# Main_board.net
KiCad netlist of a schematic drawn in Altium Designer
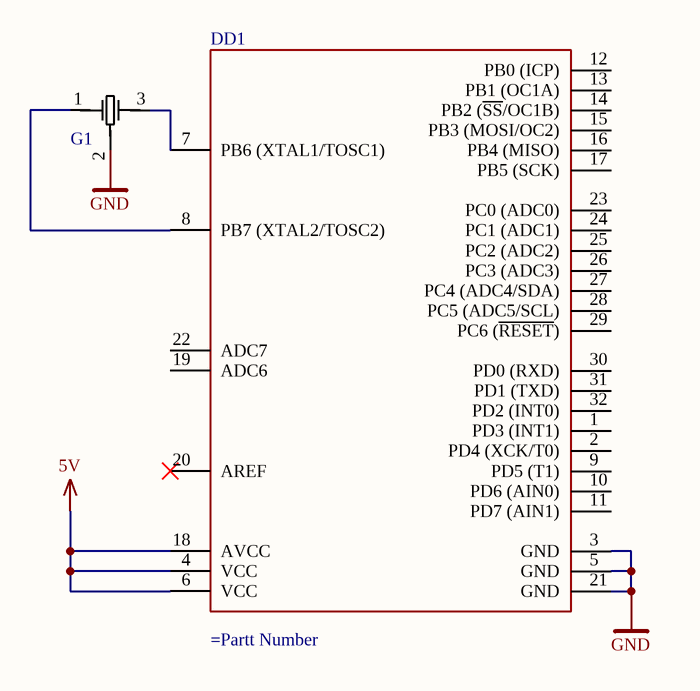
[diagram p0: Main board.SchDoc]

(export (version "E")
  (design (tool "Eeschema 10.0.6"))
  (components
    (comp (ref "DD1")
      (value "~")
      (footprint "TQFP32_N")
      (description "IC MCU 8BIT 32KB FLASH 32TQFP")
      (fields
        (field (name "PART NUMBER") "ATMEGA328")
        (field (name "DIGI-KEY PART NUMBER") "ATMEGA328PB-AU-ND")
      )
      (libsource (lib "SssAccesDatbase") (part "ATMEGA328"))
    )
    (comp (ref "G1")
      (value "8MHz 33pF")
      (footprint "CSTNE_G")
      (description "Resonators 8.0000MHz 33pF SMD CHP Resntr")
      (fields
        (field (name "PART NUMBER") "CSTNE8M00G550000R0")
        (field (name "DIGI-KEY PART NUMBER") "490-17958-1-ND")
      )
      (libsource (lib "SssAccesDatbase") (part "CSTNE_G"))
    )
  )
  (nets
    (net (code "1") (name "5V") (class "Default")
      (node (ref "DD1") (pin "18") (pinfunction "AVCC_18") (pintype "power_in"))
      (node (ref "DD1") (pin "4") (pinfunction "VCC_4") (pintype "power_in"))
      (node (ref "DD1") (pin "6") (pinfunction "VCC_6") (pintype "power_in"))
    )
    (net (code "2") (name "GND") (class "Default")
      (node (ref "DD1") (pin "21") (pinfunction "GND_21") (pintype "power_in"))
      (node (ref "DD1") (pin "3") (pinfunction "GND_3") (pintype "power_in"))
      (node (ref "DD1") (pin "5") (pinfunction "GND_5") (pintype "power_in"))
      (node (ref "G1") (pin "2") (pinfunction "2_2") (pintype "passive"))
    )
    (net (code "3") (name "Net-(DD1-PB6_(XTAL1{slash}TOSC1))") (class "Default")
      (node (ref "DD1") (pin "7") (pinfunction "PB6_(XTAL1/TOSC1)_7") (pintype "passive"))
      (node (ref "G1") (pin "3") (pinfunction "3_3") (pintype "passive"))
    )
    (net (code "4") (name "Net-(DD1-PB7_(XTAL2{slash}TOSC2))") (class "Default")
      (node (ref "DD1") (pin "8") (pinfunction "PB7_(XTAL2/TOSC2)_8") (pintype "passive"))
      (node (ref "G1") (pin "1") (pinfunction "1_1") (pintype "passive"))
    )
    (net (code "5") (name "unconnected-(DD1-ADC6-Pad19)") (class "Default")
      (node (ref "DD1") (pin "19") (pinfunction "ADC6_19") (pintype "passive"))
    )
    (net (code "6") (name "unconnected-(DD1-ADC7-Pad22)") (class "Default")
      (node (ref "DD1") (pin "22") (pinfunction "ADC7_22") (pintype "passive"))
    )
    (net (code "7") (name "unconnected-(DD1-AREF-Pad20)") (class "Default")
      (node (ref "DD1") (pin "20") (pinfunction "AREF_20") (pintype "passive+no_connect"))
    )
    (net (code "8") (name "unconnected-(DD1-PB0_(ICP)-Pad12)") (class "Default")
      (node (ref "DD1") (pin "12") (pinfunction "PB0_(ICP)_12") (pintype "passive"))
    )
    (net (code "9") (name "unconnected-(DD1-PB1_(OC1A)-Pad13)") (class "Default")
      (node (ref "DD1") (pin "13") (pinfunction "PB1_(OC1A)_13") (pintype "passive"))
    )
    (net (code "10") (name "unconnected-(DD1-PB2_(~{SS}{slash}OC1B)-Pad14)") (class "Default")
      (node (ref "DD1") (pin "14") (pinfunction "PB2_(~{SS}/OC1B)_14") (pintype "passive"))
    )
    (net (code "11") (name "unconnected-(DD1-PB3_(MOSI{slash}OC2)-Pad15)") (class "Default")
      (node (ref "DD1") (pin "15") (pinfunction "PB3_(MOSI/OC2)_15") (pintype "passive"))
    )
    (net (code "12") (name "unconnected-(DD1-PB4_(MISO)-Pad16)") (class "Default")
      (node (ref "DD1") (pin "16") (pinfunction "PB4_(MISO)_16") (pintype "passive"))
    )
    (net (code "13") (name "unconnected-(DD1-PB5_(SCK)-Pad17)") (class "Default")
      (node (ref "DD1") (pin "17") (pinfunction "PB5_(SCK)_17") (pintype "passive"))
    )
    (net (code "14") (name "unconnected-(DD1-PC0_(ADC0)-Pad23)") (class "Default")
      (node (ref "DD1") (pin "23") (pinfunction "PC0_(ADC0)_23") (pintype "passive"))
    )
    (net (code "15") (name "unconnected-(DD1-PC1_(ADC1)-Pad24)") (class "Default")
      (node (ref "DD1") (pin "24") (pinfunction "PC1_(ADC1)_24") (pintype "passive"))
    )
    (net (code "16") (name "unconnected-(DD1-PC2_(ADC2)-Pad25)") (class "Default")
      (node (ref "DD1") (pin "25") (pinfunction "PC2_(ADC2)_25") (pintype "passive"))
    )
    (net (code "17") (name "unconnected-(DD1-PC3_(ADC3)-Pad26)") (class "Default")
      (node (ref "DD1") (pin "26") (pinfunction "PC3_(ADC3)_26") (pintype "passive"))
    )
    (net (code "18") (name "unconnected-(DD1-PC4_(ADC4{slash}SDA)-Pad27)") (class "Default")
      (node (ref "DD1") (pin "27") (pinfunction "PC4_(ADC4/SDA)_27") (pintype "passive"))
    )
    (net (code "19") (name "unconnected-(DD1-PC5_(ADC5{slash}SCL)-Pad28)") (class "Default")
      (node (ref "DD1") (pin "28") (pinfunction "PC5_(ADC5/SCL)_28") (pintype "passive"))
    )
    (net (code "20") (name "unconnected-(DD1-PC6_(~{RESET})-Pad29)") (class "Default")
      (node (ref "DD1") (pin "29") (pinfunction "PC6_(~{RESET})_29") (pintype "passive"))
    )
    (net (code "21") (name "unconnected-(DD1-PD0_(RXD)-Pad30)") (class "Default")
      (node (ref "DD1") (pin "30") (pinfunction "PD0_(RXD)_30") (pintype "passive"))
    )
    (net (code "22") (name "unconnected-(DD1-PD1_(TXD)-Pad31)") (class "Default")
      (node (ref "DD1") (pin "31") (pinfunction "PD1_(TXD)_31") (pintype "passive"))
    )
    (net (code "23") (name "unconnected-(DD1-PD2_(INT0)-Pad32)") (class "Default")
      (node (ref "DD1") (pin "32") (pinfunction "PD2_(INT0)_32") (pintype "passive"))
    )
    (net (code "24") (name "unconnected-(DD1-PD3_(INT1)-Pad1)") (class "Default")
      (node (ref "DD1") (pin "1") (pinfunction "PD3_(INT1)_1") (pintype "passive"))
    )
    (net (code "25") (name "unconnected-(DD1-PD4_(XCK{slash}T0)-Pad2)") (class "Default")
      (node (ref "DD1") (pin "2") (pinfunction "PD4_(XCK/T0)_2") (pintype "passive"))
    )
    (net (code "26") (name "unconnected-(DD1-PD5_(T1)-Pad9)") (class "Default")
      (node (ref "DD1") (pin "9") (pinfunction "PD5_(T1)_9") (pintype "passive"))
    )
    (net (code "27") (name "unconnected-(DD1-PD6_(AIN0)-Pad10)") (class "Default")
      (node (ref "DD1") (pin "10") (pinfunction "PD6_(AIN0)_10") (pintype "passive"))
    )
    (net (code "28") (name "unconnected-(DD1-PD7_(AIN1)-Pad11)") (class "Default")
      (node (ref "DD1") (pin "11") (pinfunction "PD7_(AIN1)_11") (pintype "passive"))
    )
  )
)
